# Encoder_DC_Mot.net
KiCad netlist of a schematic drawn in Altium Designer
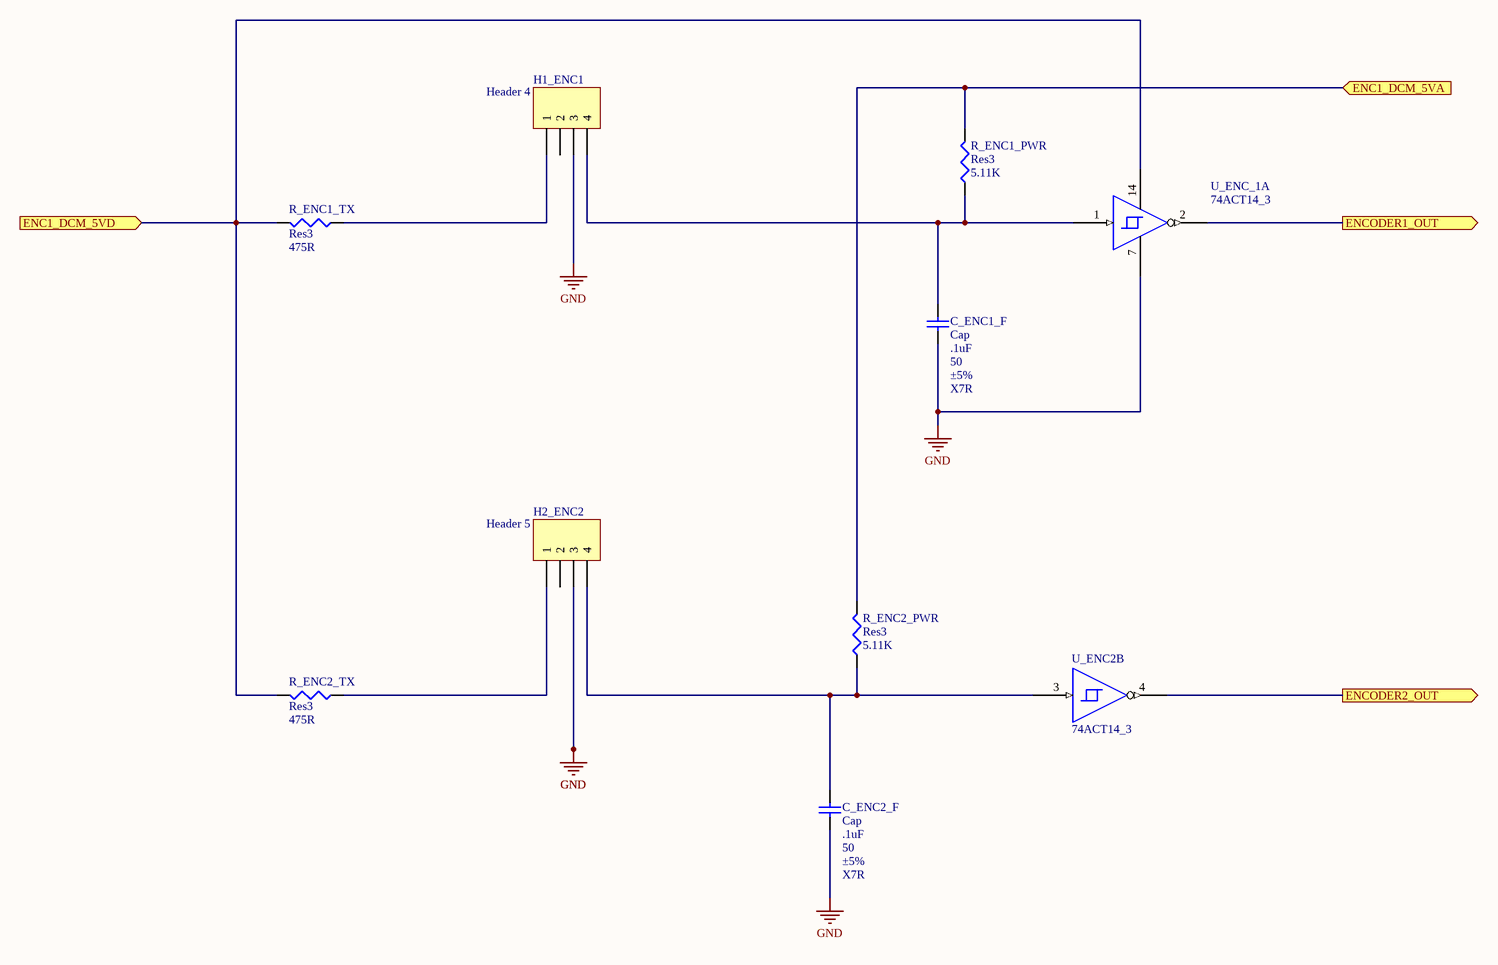
[diagram p0: Encoder_DC_Mot.SchDoc]

(export (version "E")
  (design (tool "Eeschema 10.0.6"))
  (components
    (comp (ref "C_ENC1_F")
      (value "Cap")
      (footprint "CAPC2012X09M")
      (description "CAP CER .1uF 50v X7R 0805")
      (fields
        (field (name "ALTIUM_VALUE") ".1uF")
        (field (name "WV") "50")
        (field (name "TOLERANCE") "±5%")
        (field (name "TYPE") "X7R")
        (field (name "MPN") "C0805C104J5RACTU")
      )
      (libsource (lib "esd_library") (part "CAP-X7R-.1uF-50V-±5%"))
    )
    (comp (ref "C_ENC2_F")
      (value "Cap")
      (footprint "CAPC2012X09M")
      (description "CAP CER .1uF 50v X7R 0805")
      (fields
        (field (name "ALTIUM_VALUE") ".1uF")
        (field (name "WV") "50")
        (field (name "TOLERANCE") "±5%")
        (field (name "TYPE") "X7R")
        (field (name "MPN") "C0805C104J5RACTU")
      )
      (libsource (lib "esd_library") (part "CAP-X7R-.1uF-50V-±5%"))
    )
    (comp (ref "H1_ENC1")
      (value "Header 4")
      (footprint "HDR1X4")
      (description "Header, 4-Pin")
      (fields (field (name "MPN") "PEC04SFAN"))
      (libsource (lib "esd_library") (part "Header 4"))
    )
    (comp (ref "H2_ENC2")
      (value "Header 5")
      (footprint "HDR1X4")
      (description "Header, 4-Pin")
      (fields (field (name "MPN") "PEC04SFAN"))
      (libsource (lib "esd_library") (part "Header 4"))
    )
    (comp (ref "R_ENC1_PWR")
      (value "Res3")
      (footprint "RESC2112X05M")
      (description "RES SMD 5.11K OHM 1% 1/8W 0805")
      (fields (field (name "ALTIUM_VALUE") "5.11K") (field (name "MPN") "CRCW08055K11FKEA"))
      (libsource (lib "esd_library") (part "Resistor_5.11K"))
    )
    (comp (ref "R_ENC1_TX")
      (value "Res3")
      (footprint "RESC2112X05M")
      (description "RES SMD 475R OHM 1% 1/8W 0805")
      (fields (field (name "ALTIUM_VALUE") "475R") (field (name "MPN") "CRCW0805475RFKEA"))
      (libsource (lib "esd_library") (part "Resistor_475R"))
    )
    (comp (ref "R_ENC2_PWR")
      (value "Res3")
      (footprint "RESC2112X05M")
      (description "RES SMD 5.11K OHM 1% 1/8W 0805")
      (fields (field (name "ALTIUM_VALUE") "5.11K") (field (name "MPN") "CRCW08055K11FKEA"))
      (libsource (lib "esd_library") (part "Resistor_5.11K"))
    )
    (comp (ref "R_ENC2_TX")
      (value "Res3")
      (footprint "RESC2112X05M")
      (description "RES SMD 475R OHM 1% 1/8W 0805")
      (fields (field (name "ALTIUM_VALUE") "475R") (field (name "MPN") "CRCW0805475RFKEA"))
      (libsource (lib "esd_library") (part "Resistor_475R"))
    )
    (comp (ref "U_ENC2")
      (value "74ACT14_3")
      (footprint "SOIC127P600X175-14M")
      (description "IC INVERTER HEX SCHMITT 14SOIC")
      (fields (field (name "MPN") "74ACT14SCX"))
      (libsource (lib "esd_library") (part "74ACT14_3"))
    )
    (comp (ref "U_ENC_1")
      (value "74ACT14_3")
      (footprint "SOIC127P600X175-14M")
      (description "IC INVERTER HEX SCHMITT 14SOIC")
      (fields (field (name "MPN") "74ACT14SCX"))
      (libsource (lib "esd_library") (part "74ACT14_3"))
    )
  )
  (nets
    (net (code "1") (name "/ENC1_DCM_5VA") (class "Default")
      (node (ref "R_ENC1_PWR") (pin "2") (pinfunction "2_2") (pintype "passive"))
      (node (ref "R_ENC2_PWR") (pin "2") (pinfunction "2_2") (pintype "passive"))
    )
    (net (code "2") (name "/ENC1_DCM_5VD") (class "Default")
      (node (ref "R_ENC1_TX") (pin "2") (pinfunction "2_2") (pintype "passive"))
      (node (ref "R_ENC2_TX") (pin "2") (pinfunction "2_2") (pintype "passive"))
      (node (ref "U_ENC_1") (pin "14") (pinfunction "VCC_14") (pintype "power_in"))
    )
    (net (code "3") (name "/ENCODER1_OUT") (class "Default")
      (node (ref "U_ENC_1") (pin "2") (pinfunction "Y_2") (pintype "output"))
    )
    (net (code "4") (name "/ENCODER2_OUT") (class "Default")
      (node (ref "U_ENC2") (pin "4") (pinfunction "Y_4") (pintype "output"))
    )
    (net (code "5") (name "GND") (class "Default")
      (node (ref "C_ENC1_F") (pin "1") (pinfunction "1_1") (pintype "passive"))
      (node (ref "C_ENC2_F") (pin "1") (pinfunction "1_1") (pintype "passive"))
      (node (ref "H1_ENC1") (pin "3") (pinfunction "3_3") (pintype "passive"))
      (node (ref "H2_ENC2") (pin "3") (pinfunction "3_3") (pintype "passive"))
      (node (ref "U_ENC_1") (pin "7") (pinfunction "GND_POWER_7") (pintype "power_in"))
    )
    (net (code "6") (name "Net-(H1_ENC1-Pad1)") (class "Default")
      (node (ref "H1_ENC1") (pin "1") (pinfunction "1_1") (pintype "passive"))
      (node (ref "R_ENC1_TX") (pin "1") (pinfunction "1_1") (pintype "passive"))
    )
    (net (code "7") (name "Net-(H2_ENC2-Pad1)") (class "Default")
      (node (ref "H2_ENC2") (pin "1") (pinfunction "1_1") (pintype "passive"))
      (node (ref "R_ENC2_TX") (pin "1") (pinfunction "1_1") (pintype "passive"))
    )
    (net (code "8") (name "Net-(U_ENC2B-A)") (class "Default")
      (node (ref "C_ENC2_F") (pin "2") (pinfunction "2_2") (pintype "passive"))
      (node (ref "H2_ENC2") (pin "4") (pinfunction "4_4") (pintype "passive"))
      (node (ref "R_ENC2_PWR") (pin "1") (pinfunction "1_1") (pintype "passive"))
      (node (ref "U_ENC2") (pin "3") (pinfunction "A_3") (pintype "input"))
    )
    (net (code "9") (name "Net-(U_ENC_1A-A)") (class "Default")
      (node (ref "C_ENC1_F") (pin "2") (pinfunction "2_2") (pintype "passive"))
      (node (ref "H1_ENC1") (pin "4") (pinfunction "4_4") (pintype "passive"))
      (node (ref "R_ENC1_PWR") (pin "1") (pinfunction "1_1") (pintype "passive"))
      (node (ref "U_ENC_1") (pin "1") (pinfunction "A_1") (pintype "input"))
    )
    (net (code "10") (name "unconnected-(H1_ENC1-Pad2)") (class "Default")
      (node (ref "H1_ENC1") (pin "2") (pinfunction "2_2") (pintype "passive"))
    )
    (net (code "11") (name "unconnected-(H2_ENC2-Pad2)") (class "Default")
      (node (ref "H2_ENC2") (pin "2") (pinfunction "2_2") (pintype "passive"))
    )
  )
)
